# as5311_tsb.net
KiCad netlist of a schematic drawn in Altium Designer
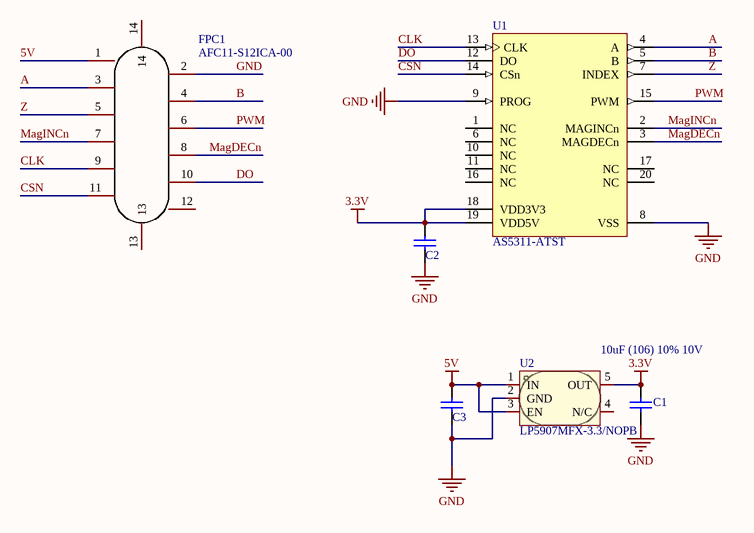
[diagram p0: as5311_tsb.SchDoc]

(export (version "E")
  (design (tool "Eeschema 10.0.6"))
  (components
    (comp (ref "C1")
      (value "10uF (106) 10% 10V")
      (footprint "0603_C")
      (description "贴片电容")
      (libsource (lib "Miscellaneous Devices LC") (part "0603 10uF (106) 10% 10V"))
    )
    (comp (ref "C2")
      (value "100nF (104) 10% 50V")
      (footprint "0603_C")
      (description "贴片电容")
      (libsource (lib "Miscellaneous Devices LC") (part "0603 100nF (104) 10% 50V"))
    )
    (comp (ref "C3")
      (value "100nF (104) 10% 50V")
      (footprint "0603_C")
      (description "贴片电容")
      (libsource (lib "Miscellaneous Devices LC") (part "0603 100nF (104) 10% 50V"))
    )
    (comp (ref "FPC1")
      (value "AFC11-S12ICA-00")
      (footprint "CONN-SMD-12P_AFC11-S12ICA-00")
      (description "AFC11-S12ICA-00，间距:0.5mm;触点数量:12P;锁定特性:抽屉式;触点类型:单侧触点/垂直;安装类型:立贴;")
      (fields (field (name "MANUFACTURER") "JS(钜硕电子)") (field (name "NAME") "AFC11-S12ICA-00"))
      (libsource (lib "MyLib") (part "FPC-12PIN-0.5-立贴"))
    )
    (comp (ref "U1")
      (value "AS5311-ATST")
      (footprint "AMS-TSSOP-20-6500X4400DE_A_L")
      (fields (field (name "MANUFACTURER") "AMS") (field (name "MANUFACTURER_1") "ams TAOS"))
      (libsource (lib "MyLib") (part "AS5311"))
    )
    (comp (ref "U2")
      (value "LP5907MFX-3.3/NOPB")
      (footprint "SOT-23-5_L3.0-W1.7-P0.95-LS2.8-BR")
      (description "输出类型:固定;输出极性:正;最大输入电压:5.5V;输出电压:3.3V;输出电流:250mA;电源纹波抑制比(PSRR):90dB;")
      (fields (field (name "MANUFACTURER") "TI(德州仪器)") (field (name "NAME") "LP5907MFX-3.3/NOPB"))
      (libsource (lib "MyLib") (part "LP5907MFX-3.3/NOPB"))
    )
  )
  (nets
    (net (code "1") (name "/A") (class "Default")
      (node (ref "FPC1") (pin "3") (pinfunction "3_3") (pintype "passive"))
      (node (ref "U1") (pin "4") (pinfunction "A_4") (pintype "output"))
    )
    (net (code "2") (name "/B") (class "Default")
      (node (ref "FPC1") (pin "4") (pinfunction "4_4") (pintype "passive"))
      (node (ref "U1") (pin "5") (pinfunction "B_5") (pintype "output"))
    )
    (net (code "3") (name "/CLK") (class "Default")
      (node (ref "FPC1") (pin "9") (pinfunction "9_9") (pintype "passive"))
      (node (ref "U1") (pin "13") (pinfunction "CLK_13") (pintype "input"))
    )
    (net (code "4") (name "/CSN") (class "Default")
      (node (ref "FPC1") (pin "11") (pinfunction "11_11") (pintype "passive"))
      (node (ref "U1") (pin "14") (pinfunction "CSn_14") (pintype "input"))
    )
    (net (code "5") (name "/DO") (class "Default")
      (node (ref "FPC1") (pin "10") (pinfunction "10_10") (pintype "passive"))
      (node (ref "U1") (pin "12") (pinfunction "DO_12") (pintype "tri_state"))
    )
    (net (code "6") (name "/MagDECn") (class "Default")
      (node (ref "FPC1") (pin "8") (pinfunction "8_8") (pintype "passive"))
      (node (ref "U1") (pin "3") (pinfunction "MAGDECn_3") (pintype "open_collector"))
    )
    (net (code "7") (name "/MagINCn") (class "Default")
      (node (ref "FPC1") (pin "7") (pinfunction "7_7") (pintype "passive"))
      (node (ref "U1") (pin "2") (pinfunction "MAGINCn_2") (pintype "open_collector"))
    )
    (net (code "8") (name "/PWM") (class "Default")
      (node (ref "FPC1") (pin "6") (pinfunction "6_6") (pintype "passive"))
      (node (ref "U1") (pin "15") (pinfunction "PWM_15") (pintype "output"))
    )
    (net (code "9") (name "/Z") (class "Default")
      (node (ref "FPC1") (pin "5") (pinfunction "5_5") (pintype "passive"))
      (node (ref "U1") (pin "7") (pinfunction "INDEX_7") (pintype "output"))
    )
    (net (code "10") (name "3.3V") (class "Default")
      (node (ref "C1") (pin "2") (pinfunction "2_2") (pintype "passive"))
      (node (ref "C2") (pin "2") (pinfunction "2_2") (pintype "passive"))
      (node (ref "U1") (pin "18") (pinfunction "VDD3V3_18") (pintype "power_in"))
      (node (ref "U1") (pin "19") (pinfunction "VDD5V_19") (pintype "power_in"))
      (node (ref "U2") (pin "5") (pinfunction "OUT_5") (pintype "passive"))
    )
    (net (code "11") (name "5V") (class "Default")
      (node (ref "C3") (pin "2") (pinfunction "2_2") (pintype "passive"))
      (node (ref "FPC1") (pin "1") (pinfunction "1_1") (pintype "passive"))
      (node (ref "U2") (pin "1") (pinfunction "IN_1") (pintype "passive"))
      (node (ref "U2") (pin "3") (pinfunction "EN_3") (pintype "passive"))
    )
    (net (code "12") (name "GND") (class "Default")
      (node (ref "C1") (pin "1") (pinfunction "1_1") (pintype "passive"))
      (node (ref "C2") (pin "1") (pinfunction "1_1") (pintype "passive"))
      (node (ref "C3") (pin "1") (pinfunction "1_1") (pintype "passive"))
      (node (ref "FPC1") (pin "2") (pinfunction "2_2") (pintype "passive"))
      (node (ref "U1") (pin "8") (pinfunction "VSS_8") (pintype "power_in"))
      (node (ref "U1") (pin "9") (pinfunction "PROG_9") (pintype "input"))
      (node (ref "U2") (pin "2") (pinfunction "GND_2") (pintype "passive"))
    )
    (net (code "13") (name "unconnected-(FPC1-Pad12)") (class "Default")
      (node (ref "FPC1") (pin "12") (pinfunction "12_12") (pintype "passive"))
    )
    (net (code "14") (name "unconnected-(FPC1-Pad13)") (class "Default")
      (node (ref "FPC1") (pin "13") (pinfunction "13_13") (pintype "passive"))
    )
    (net (code "15") (name "unconnected-(FPC1-Pad14)") (class "Default")
      (node (ref "FPC1") (pin "14") (pinfunction "14_14") (pintype "passive"))
    )
    (net (code "16") (name "unconnected-(U1-NC-Pad1)") (class "Default")
      (node (ref "U1") (pin "1") (pinfunction "NC_1") (pintype "passive"))
    )
    (net (code "17") (name "unconnected-(U1-NC-Pad6)") (class "Default")
      (node (ref "U1") (pin "6") (pinfunction "NC_6") (pintype "passive"))
    )
    (net (code "18") (name "unconnected-(U1-NC-Pad10)") (class "Default")
      (node (ref "U1") (pin "10") (pinfunction "NC_10") (pintype "passive"))
    )
    (net (code "19") (name "unconnected-(U1-NC-Pad11)") (class "Default")
      (node (ref "U1") (pin "11") (pinfunction "NC_11") (pintype "passive"))
    )
    (net (code "20") (name "unconnected-(U1-NC-Pad16)") (class "Default")
      (node (ref "U1") (pin "16") (pinfunction "NC_16") (pintype "passive"))
    )
    (net (code "21") (name "unconnected-(U1-NC-Pad17)") (class "Default")
      (node (ref "U1") (pin "17") (pinfunction "NC_17") (pintype "passive"))
    )
    (net (code "22") (name "unconnected-(U1-NC-Pad20)") (class "Default")
      (node (ref "U1") (pin "20") (pinfunction "NC_20") (pintype "passive"))
    )
    (net (code "23") (name "unconnected-(U2-N{slash}C-Pad4)") (class "Default")
      (node (ref "U2") (pin "4") (pinfunction "N/C_4") (pintype "passive"))
    )
  )
)
